# Connectors.net
KiCad netlist of a schematic drawn in Altium Designer
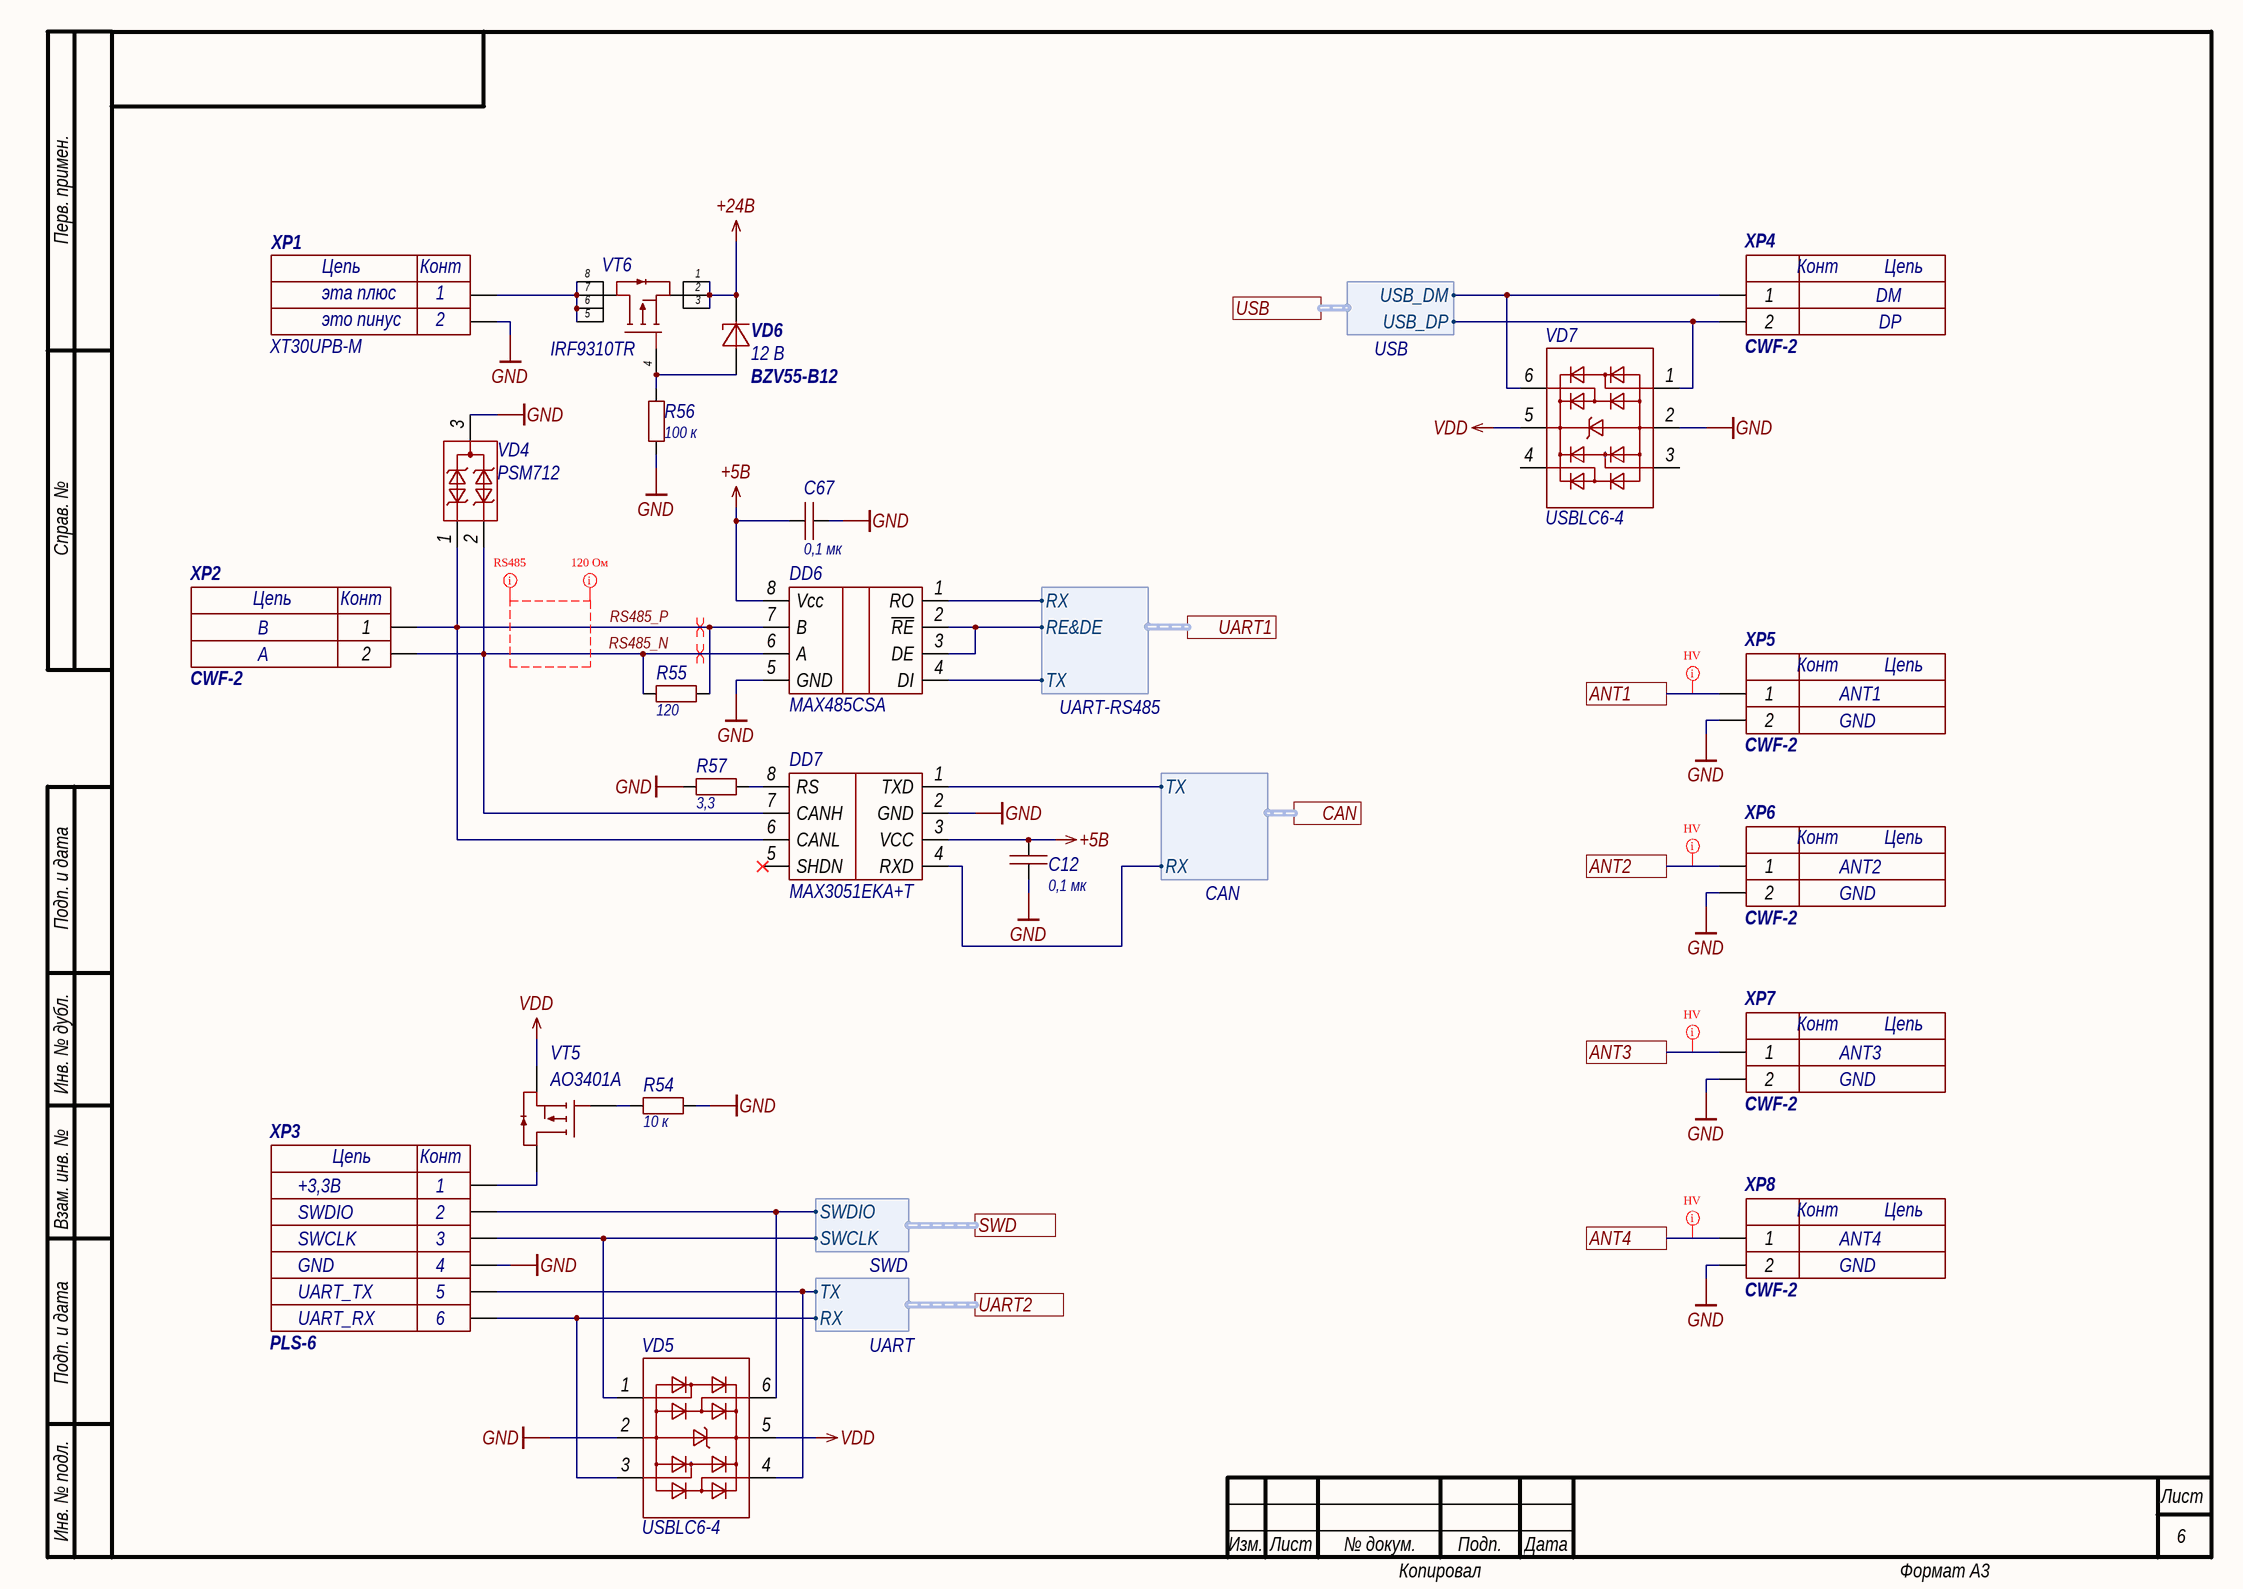
[diagram p0: Connectors.SchDoc]

(export (version "E")
  (design (tool "Eeschema 10.0.6"))
  (components
    (comp (ref "C12")
      (value "0,1 мк")
      (footprint "0603C")
      (description "Конденсатор 0603C ёмкостью 0,1 мк 10%, 50 В, X7R")
      (fields (field (name "PART NUMBER") "Capacitor_0,1u_10_50V_X7R_0603C") (field (name "TOLERANCE") "10%"))
      (libsource (lib "Hydrolib") (part "Capacitor"))
    )
    (comp (ref "C67")
      (value "0,1 мк")
      (footprint "0603C")
      (description "Конденсатор 0603C ёмкостью 0,1 мк 10%, 50 В, X7R")
      (fields (field (name "PART NUMBER") "Capacitor_0,1u_10_50V_X7R_0603C") (field (name "TOLERANCE") "10%"))
      (libsource (lib "Hydrolib") (part "Capacitor"))
    )
    (comp (ref "DD6")
      (value "MAX485CSA")
      (footprint "SOIC-8")
      (description "RS-485 приёмопередатчик")
      (libsource (lib "Hydrolib") (part "MAX485CSA"))
    )
    (comp (ref "DD7")
      (value "MAX3051EKA+T")
      (footprint "SOT23-8")
      (description "CAN трансивер 1Mbps +3.3В")
      (fields (field (name "АВТОР") "glebmih"))
      (libsource (lib "Hydrolib") (part "MAX3051EKA+T"))
    )
    (comp (ref "R54")
      (value "10 к")
      (footprint "0603R")
      (description "Резистор номиналом 10 кОм 1%")
      (fields (field (name "PART NUMBER") "Resistor_10k_1_0603") (field (name "TOLERANCE") "1%"))
      (libsource (lib "") (part "Resistor_2"))
    )
    (comp (ref "R55")
      (value "120")
      (footprint "1206R")
      (description "Резистор номиналом 120 Ом 1%")
      (fields
        (field (name "PART NUMBER") "Resistor_120_1_1206")
        (field (name "TOLERANCE") "1%")
        (field (name "АВТОР") "glebmih")
      )
      (libsource (lib "Hydrolib") (part "Resistor"))
    )
    (comp (ref "R56")
      (value "100 к")
      (footprint "0603R")
      (description "Резистор номиналом 100 кОм 1%")
      (fields (field (name "PART NUMBER") "Resistor_100k_1_0603") (field (name "TOLERANCE") "1%"))
      (libsource (lib "") (part "Resistor_1"))
    )
    (comp (ref "R57")
      (value "3,3")
      (footprint "0603R")
      (description "Резистор номиналом 3,3 Ом 1%")
      (fields (field (name "PART NUMBER") "Resistor_3.3_1_0603") (field (name "TOLERANCE") "1%"))
      (libsource (lib "Hydrolib") (part "Resistor"))
    )
    (comp (ref "VD4")
      (value "PSM712")
      (footprint "SOT23-3")
      (description "Защитный диод для линии RS-485")
      (libsource (lib "Hydrolib") (part "TVS_2_2dir"))
    )
    (comp (ref "VD5")
      (value "USBLC6-4")
      (footprint "SOT23-6")
      (description "Сборка защитных диодов для USB")
      (libsource (lib "Hydrolib") (part "USBLC6-4"))
    )
    (comp (ref "VD6")
      (value "BZV55-B12")
      (footprint "mini_MELF_3.5mm")
      (description "Стабилитрон 12В, 5%, 0.5Вт")
      (fields (field (name "ALTIUM_VALUE") "12 В") (field (name "АВТОР") "rreali"))
      (libsource (lib "Hydrolib") (part "Zener"))
    )
    (comp (ref "VD7")
      (value "USBLC6-4")
      (footprint "SOT23-6")
      (description "Сборка защитных диодов для USB")
      (libsource (lib "Hydrolib") (part "USBLC6-4"))
    )
    (comp (ref "VT5")
      (value "AO3401A")
      (footprint "SOT23-3")
      (description "P-канальный MOSFET")
      (libsource (lib "Hydrolib") (part "MOSFET P-channel 2"))
    )
    (comp (ref "VT6")
      (value "IRF9310TR")
      (footprint "SOIC-8")
      (description "P-канальный MOSFET, 30 В, 20 А")
      (fields (field (name "АВТОР") "glebmih"))
      (libsource (lib "Hydrolib") (part "MOSFET_P-channel_8pin"))
    )
    (comp (ref "XP1")
      (value "XT30UPB-M")
      (footprint "XT30UPB-M")
      (description "2-пиновый разъем с ключом")
      (fields
        (field (name "VALUE2") "это пинус")
        (field (name "VALUE1") "эта плюс")
        (field (name "АВТОР") "rreali")
      )
      (libsource (lib "Hydrolib") (part "Polar_Conn"))
    )
    (comp (ref "XP2")
      (value "CWF-2")
      (footprint "CWF-2")
      (description "2-пиновый разъем с ключом")
      (fields (field (name "АВТОР") "rreali"))
      (libsource (lib "Hydrolib") (part "Conn_2pin"))
    )
    (comp (ref "XP3")
      (value "PLS-6")
      (footprint "PLS6")
      (description "Гребенка 6 пинов")
      (fields (field (name "АВТОР") "glebmih"))
      (libsource (lib "Hydrolib") (part "Conn_6pin"))
    )
    (comp (ref "XP4")
      (value "CWF-2")
      (footprint "CWF-2")
      (description "2-пиновый разъем с ключом")
      (fields (field (name "VALUE2") "DP") (field (name "VALUE1") "DM") (field (name "АВТОР") "rreali"))
      (libsource (lib "Hydrolib") (part "Conn_2pin"))
    )
    (comp (ref "XP5")
      (value "CWF-2")
      (footprint "CWF-2")
      (description "2-пиновый разъем с ключом")
      (fields (field (name "АВТОР") "rreali"))
      (libsource (lib "Hydrolib") (part "Conn_2pin"))
    )
    (comp (ref "XP6")
      (value "CWF-2")
      (footprint "CWF-2")
      (description "2-пиновый разъем с ключом")
      (fields (field (name "АВТОР") "rreali"))
      (libsource (lib "Hydrolib") (part "Conn_2pin"))
    )
    (comp (ref "XP7")
      (value "CWF-2")
      (footprint "CWF-2")
      (description "2-пиновый разъем с ключом")
      (fields (field (name "АВТОР") "rreali"))
      (libsource (lib "Hydrolib") (part "Conn_2pin"))
    )
    (comp (ref "XP8")
      (value "CWF-2")
      (footprint "CWF-2")
      (description "2-пиновый разъем с ключом")
      (fields (field (name "АВТОР") "rreali"))
      (libsource (lib "Hydrolib") (part "Conn_2pin"))
    )
  )
  (nets
    (net (code "6") (name "+5В") (class "Default")
      (node (ref "C12") (pin "2") (pinfunction "2_2") (pintype "passive"))
      (node (ref "C67") (pin "1") (pinfunction "1_1") (pintype "passive"))
      (node (ref "DD6") (pin "8") (pinfunction "Vcc_8") (pintype "passive"))
      (node (ref "DD7") (pin "3") (pinfunction "VCC_3") (pintype "passive"))
    )
    (net (code "7") (name "+24В") (class "Default")
      (node (ref "VD6") (pin "2") (pinfunction "2_2") (pintype "passive"))
      (node (ref "VT6") (pin "1") (pinfunction "1_1") (pintype "passive"))
      (node (ref "VT6") (pin "2") (pinfunction "2_2") (pintype "passive"))
      (node (ref "VT6") (pin "3") (pinfunction "3_3") (pintype "passive"))
    )
    (net (code "8") (name "/ANT1") (class "Default")
      (node (ref "XP5") (pin "1") (pinfunction "1_1") (pintype "passive"))
    )
    (net (code "9") (name "/ANT2") (class "Default")
      (node (ref "XP6") (pin "1") (pinfunction "1_1") (pintype "passive"))
    )
    (net (code "10") (name "/ANT3") (class "Default")
      (node (ref "XP7") (pin "1") (pinfunction "1_1") (pintype "passive"))
    )
    (net (code "11") (name "/ANT4") (class "Default")
      (node (ref "XP8") (pin "1") (pinfunction "1_1") (pintype "passive"))
    )
    (net (code "12") (name "/RE&DE") (class "Default")
      (node (ref "DD6") (pin "2") (pinfunction "~{RE}_2") (pintype "passive"))
      (node (ref "DD6") (pin "3") (pinfunction "DE_3") (pintype "passive"))
    )
    (net (code "13") (name "/RS485_N") (class "Default")
      (node (ref "DD6") (pin "6") (pinfunction "A_6") (pintype "passive"))
      (node (ref "DD7") (pin "7") (pinfunction "CANH_7") (pintype "passive"))
      (node (ref "R55") (pin "1") (pinfunction "1_1") (pintype "passive"))
      (node (ref "VD4") (pin "2") (pinfunction "15_2") (pintype "passive"))
      (node (ref "XP2") (pin "2") (pinfunction "2_2") (pintype "passive"))
    )
    (net (code "14") (name "/RS485_P") (class "Default")
      (node (ref "DD6") (pin "7") (pinfunction "B_7") (pintype "passive"))
      (node (ref "DD7") (pin "6") (pinfunction "CANL_6") (pintype "passive"))
      (node (ref "R55") (pin "2") (pinfunction "2_2") (pintype "passive"))
      (node (ref "VD4") (pin "1") (pinfunction "14_1") (pintype "passive"))
      (node (ref "XP2") (pin "1") (pinfunction "1_1") (pintype "passive"))
    )
    (net (code "15") (name "/SWCLK") (class "Default")
      (node (ref "VD5") (pin "1") (pinfunction "9_1") (pintype "passive"))
      (node (ref "XP3") (pin "3") (pinfunction "3_3") (pintype "passive"))
    )
    (net (code "16") (name "/SWDIO") (class "Default")
      (node (ref "VD5") (pin "6") (pinfunction "14_6") (pintype "passive"))
      (node (ref "XP3") (pin "2") (pinfunction "2_2") (pintype "passive"))
    )
    (net (code "17") (name "/USB_DM") (class "Default")
      (node (ref "VD7") (pin "6") (pinfunction "14_6") (pintype "passive"))
      (node (ref "XP4") (pin "1") (pinfunction "1_1") (pintype "passive"))
    )
    (net (code "18") (name "/USB_DP") (class "Default")
      (node (ref "VD7") (pin "1") (pinfunction "9_1") (pintype "passive"))
      (node (ref "XP4") (pin "2") (pinfunction "2_2") (pintype "passive"))
    )
    (net (code "24") (name "GND") (class "Default")
      (node (ref "C12") (pin "1") (pinfunction "1_1") (pintype "passive"))
      (node (ref "C67") (pin "2") (pinfunction "2_2") (pintype "passive"))
      (node (ref "DD6") (pin "5") (pinfunction "GND_5") (pintype "passive"))
      (node (ref "DD7") (pin "2") (pinfunction "GND_2") (pintype "passive"))
      (node (ref "R54") (pin "1") (pinfunction "1_1") (pintype "passive"))
      (node (ref "R56") (pin "1") (pinfunction "1_1") (pintype "passive"))
      (node (ref "R57") (pin "1") (pinfunction "1_1") (pintype "passive"))
      (node (ref "VD4") (pin "3") (pinfunction "16_3") (pintype "passive"))
      (node (ref "VD5") (pin "2") (pinfunction "10_2") (pintype "passive"))
      (node (ref "VD7") (pin "2") (pinfunction "10_2") (pintype "passive"))
      (node (ref "XP1") (pin "N") (pinfunction "N_N") (pintype "passive"))
      (node (ref "XP3") (pin "4") (pinfunction "4_4") (pintype "passive"))
      (node (ref "XP5") (pin "2") (pinfunction "2_2") (pintype "passive"))
      (node (ref "XP6") (pin "2") (pinfunction "2_2") (pintype "passive"))
      (node (ref "XP7") (pin "2") (pinfunction "2_2") (pintype "passive"))
      (node (ref "XP8") (pin "2") (pinfunction "2_2") (pintype "passive"))
    )
    (net (code "25") (name "Net-(DD7-RS)") (class "Default")
      (node (ref "DD7") (pin "8") (pinfunction "RS_8") (pintype "passive"))
      (node (ref "R57") (pin "2") (pinfunction "2_2") (pintype "passive"))
    )
    (net (code "26") (name "Net-(R54-Pad2)") (class "Default")
      (node (ref "R54") (pin "2") (pinfunction "2_2") (pintype "passive"))
      (node (ref "VT5") (pin "1") (pinfunction "1_1") (pintype "passive"))
    )
    (net (code "27") (name "Net-(R56-Pad2)") (class "Default")
      (node (ref "R56") (pin "2") (pinfunction "2_2") (pintype "passive"))
      (node (ref "VD6") (pin "1") (pinfunction "1_1") (pintype "passive"))
      (node (ref "VT6") (pin "4") (pinfunction "4_4") (pintype "passive"))
    )
    (net (code "28") (name "Net-(VD5-11)") (class "Default")
      (node (ref "VD5") (pin "3") (pinfunction "11_3") (pintype "passive"))
      (node (ref "XP3") (pin "6") (pinfunction "6_6") (pintype "passive"))
    )
    (net (code "29") (name "Net-(VD5-12)") (class "Default")
      (node (ref "VD5") (pin "4") (pinfunction "12_4") (pintype "passive"))
      (node (ref "XP3") (pin "5") (pinfunction "5_5") (pintype "passive"))
    )
    (net (code "30") (name "Net-(VT5-Pad3)") (class "Default")
      (node (ref "VT5") (pin "3") (pinfunction "3_3") (pintype "passive"))
      (node (ref "XP3") (pin "1") (pinfunction "1_1") (pintype "passive"))
    )
    (net (code "31") (name "Net-(VT6-Pad5)") (class "Default")
      (node (ref "VT6") (pin "5") (pinfunction "5_5") (pintype "passive"))
      (node (ref "VT6") (pin "6") (pinfunction "6_6") (pintype "passive"))
      (node (ref "VT6") (pin "7") (pinfunction "7_7") (pintype "passive"))
      (node (ref "VT6") (pin "8") (pinfunction "8_8") (pintype "passive"))
      (node (ref "XP1") (pin "P") (pinfunction "P_P") (pintype "passive"))
    )
    (net (code "32") (name "VDD") (class "Default")
      (node (ref "VD5") (pin "5") (pinfunction "13_5") (pintype "passive"))
      (node (ref "VD7") (pin "5") (pinfunction "13_5") (pintype "passive"))
      (node (ref "VT5") (pin "2") (pinfunction "2_2") (pintype "passive"))
    )
    (net (code "33") (name "unconnected-(DD6-DI-Pad4)") (class "Default")
      (node (ref "DD6") (pin "4") (pinfunction "DI_4") (pintype "passive"))
    )
    (net (code "34") (name "unconnected-(DD6-RO-Pad1)") (class "Default")
      (node (ref "DD6") (pin "1") (pinfunction "RO_1") (pintype "passive"))
    )
    (net (code "35") (name "unconnected-(DD7-RXD-Pad4)") (class "Default")
      (node (ref "DD7") (pin "4") (pinfunction "RXD_4") (pintype "passive"))
    )
    (net (code "36") (name "unconnected-(DD7-SHDN-Pad5)") (class "Default")
      (node (ref "DD7") (pin "5") (pinfunction "SHDN_5") (pintype "passive+no_connect"))
    )
    (net (code "37") (name "unconnected-(DD7-TXD-Pad1)") (class "Default")
      (node (ref "DD7") (pin "1") (pinfunction "TXD_1") (pintype "passive"))
    )
    (net (code "38") (name "unconnected-(VD7-11-Pad3)") (class "Default")
      (node (ref "VD7") (pin "3") (pinfunction "11_3") (pintype "passive"))
    )
    (net (code "39") (name "unconnected-(VD7-12-Pad4)") (class "Default")
      (node (ref "VD7") (pin "4") (pinfunction "12_4") (pintype "passive"))
    )
  )
)
